# BLDC_DRIVER.net
KiCad netlist of a schematic drawn in EasyEDA Pro
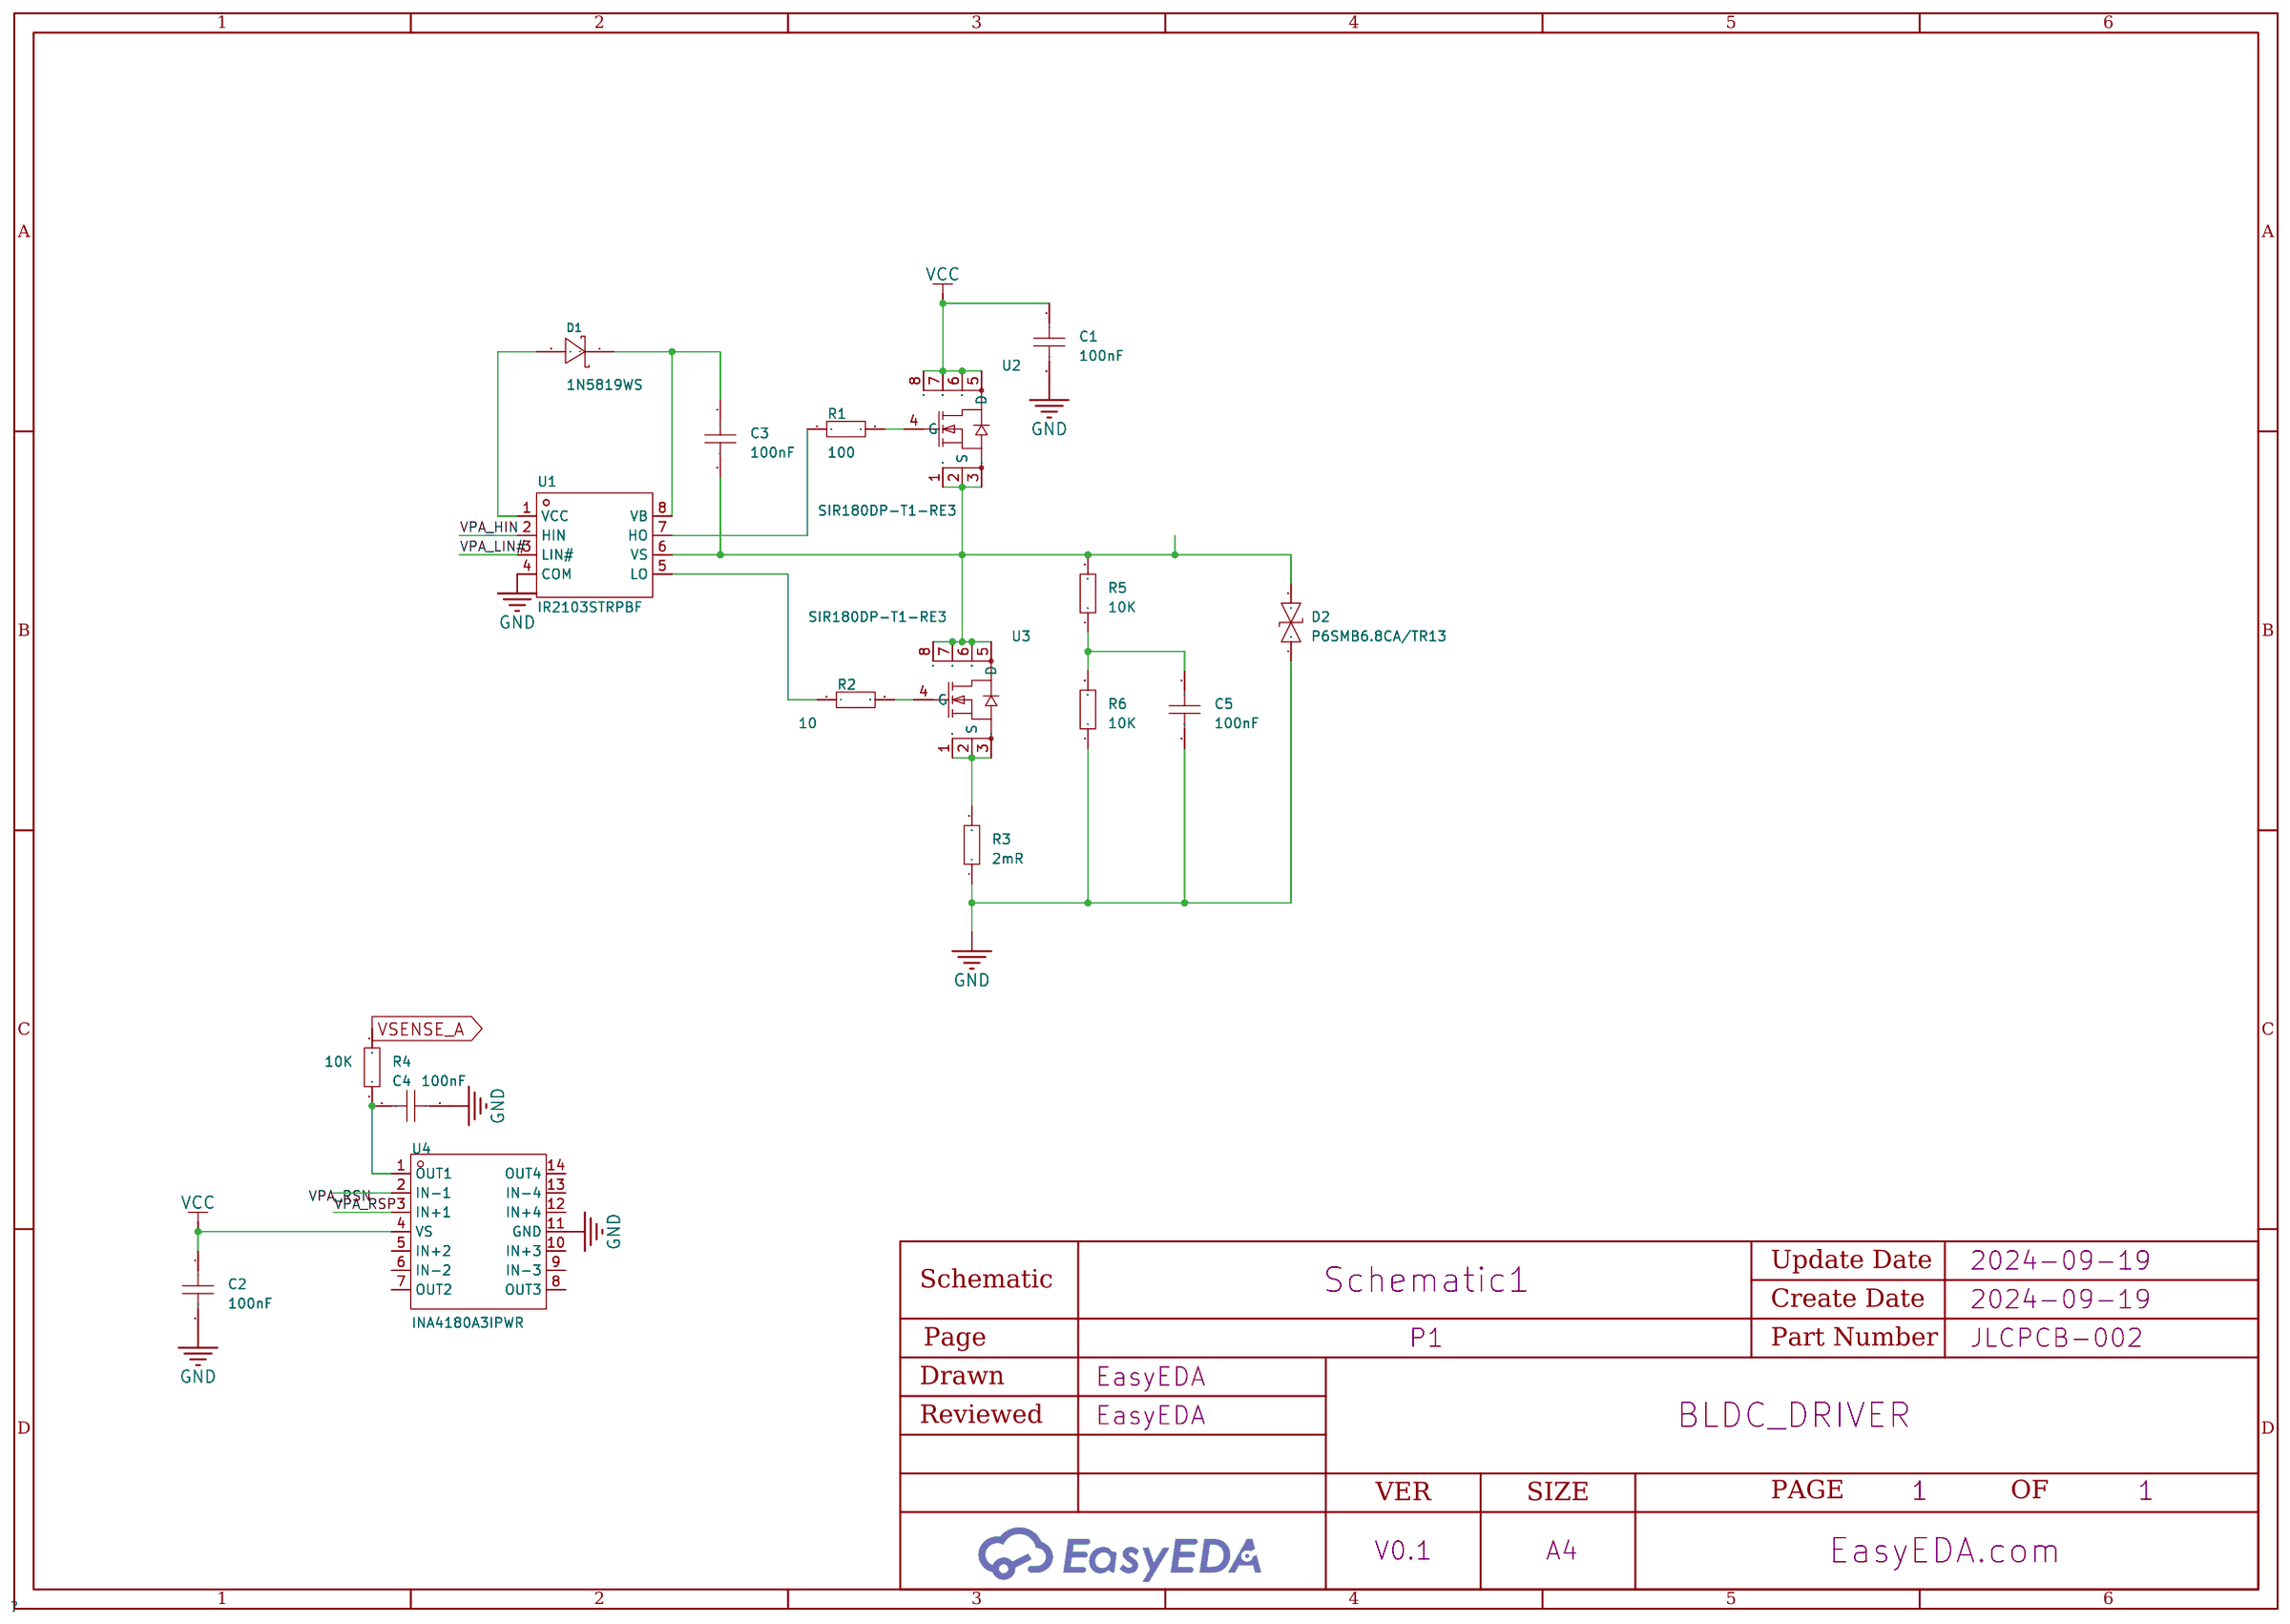
[diagram p0: schematic sheet]

(export (version "E")
  (design (tool "Eeschema 10.0.6"))
  (components
    (comp (ref "C1")
      (value "100nF")
      (footprint "easyedapro:C0603")
      (libsource (lib "easyedapro") (part "CAP"))
    )
    (comp (ref "C2")
      (value "100nF")
      (footprint "easyedapro:C0603")
      (libsource (lib "easyedapro") (part "CAP"))
    )
    (comp (ref "C3")
      (value "100nF")
      (footprint "easyedapro:C0603")
      (libsource (lib "easyedapro") (part "CAP"))
    )
    (comp (ref "C4")
      (value "100nF")
      (footprint "easyedapro:C0603")
      (libsource (lib "easyedapro") (part "CAP"))
    )
    (comp (ref "C5")
      (value "100nF")
      (footprint "easyedapro:C0603")
      (libsource (lib "easyedapro") (part "CAP"))
    )
    (comp (ref "D1")
      (value "1N5819WS")
      (footprint "easyedapro:SOD-323_L1.8-W1.3-LS2.5-RD")
      (description "Forward Voltage (Vf@If):600mV@1A Reverse Voltage (Vr):40V Average Rectified Current (Io):1A")
      (fields (field (name "Manufacturer") "Hottech(合科泰)"))
      (libsource (lib "easyedapro") (part "1N5819WS"))
    )
    (comp (ref "D2")
      (value "P6SMB6.8CA/TR13")
      (footprint "easyedapro:SMB_L4.6-W3.6-LS5.3-BI")
      (fields (field (name "Manufacturer") "Brightking(君耀电子)"))
      (libsource (lib "easyedapro") (part "P6SMB6.8CA-C78395"))
    )
    (comp (ref "R1") (value "100") (footprint "easyedapro:R0603") (libsource (lib "easyedapro") (part "Res")))
    (comp (ref "R2") (value "10") (footprint "easyedapro:R0603") (libsource (lib "easyedapro") (part "Res")))
    (comp (ref "R3") (value "2mR") (footprint "easyedapro:R0603") (libsource (lib "easyedapro") (part "Res")))
    (comp (ref "R4") (value "10K") (footprint "easyedapro:R0603") (libsource (lib "easyedapro") (part "Res")))
    (comp (ref "R5") (value "10K") (footprint "easyedapro:R0603") (libsource (lib "easyedapro") (part "Res")))
    (comp (ref "R6") (value "10K") (footprint "easyedapro:R0603") (libsource (lib "easyedapro") (part "Res")))
    (comp (ref "U1")
      (value "IR2103STRPBF")
      (footprint "easyedapro:SOIC-8_L4.9-W3.9-P1.27-LS6.0-BL")
      (fields (field (name "Manufacturer") "Infineon(英飞凌)"))
      (libsource (lib "easyedapro") (part "IR2103STRPBF"))
    )
    (comp (ref "U2")
      (value "SIR180DP-T1-RE3")
      (footprint "easyedapro:POWERPAK-SO-8_L5.9-W4.9-P1.27-LS6.2-BL")
      (fields (field (name "Manufacturer") "VISHAY(威世)"))
      (libsource (lib "easyedapro") (part "SIR180DP-T1-RE3"))
    )
    (comp (ref "U3")
      (value "SIR180DP-T1-RE3")
      (footprint "easyedapro:POWERPAK-SO-8_L5.9-W4.9-P1.27-LS6.2-BL")
      (fields (field (name "Manufacturer") "VISHAY(威世)"))
      (libsource (lib "easyedapro") (part "SIR180DP-T1-RE3"))
    )
    (comp (ref "U4")
      (value "INA4180A3IPWR")
      (footprint "easyedapro:TSSOP-14_L5.0-W4.4-P0.65-LS6.4-BL")
      (fields (field (name "Manufacturer") "TI(德州仪器)"))
      (libsource (lib "easyedapro") (part "INA4180A3IPWR"))
    )
  )
  (nets
    (net (code "1") (name "/VPA_HIN") (class "Default")
      (node (ref "U1") (pin "2") (pinfunction "HIN_2") (pintype "unspecified"))
    )
    (net (code "2") (name "/VPA_LIN#") (class "Default")
      (node (ref "U1") (pin "3") (pinfunction "LIN#_3") (pintype "unspecified"))
    )
    (net (code "3") (name "/VPA_RSN") (class "Default")
      (node (ref "U4") (pin "2") (pinfunction "IN-1_2") (pintype "unspecified"))
    )
    (net (code "4") (name "/VPA_RSP") (class "Default")
      (node (ref "U4") (pin "3") (pinfunction "IN+1_3") (pintype "unspecified"))
    )
    (net (code "5") (name "GND") (class "Default")
      (node (ref "C1") (pin "2") (pinfunction "2_2") (pintype "input"))
      (node (ref "C2") (pin "2") (pinfunction "2_2") (pintype "input"))
      (node (ref "C4") (pin "2") (pinfunction "2_2") (pintype "input"))
      (node (ref "C5") (pin "2") (pinfunction "2_2") (pintype "input"))
      (node (ref "D2") (pin "1") (pinfunction "1_1") (pintype "unspecified"))
      (node (ref "R3") (pin "1") (pinfunction "1_1") (pintype "input"))
      (node (ref "R6") (pin "1") (pinfunction "1_1") (pintype "input"))
      (node (ref "U1") (pin "4") (pinfunction "COM_4") (pintype "unspecified"))
      (node (ref "U4") (pin "11") (pinfunction "GND_11") (pintype "unspecified"))
    )
    (net (code "6") (name "Net-(C5-Pad1)") (class "Default")
      (node (ref "C5") (pin "1") (pinfunction "1_1") (pintype "input"))
      (node (ref "R5") (pin "1") (pinfunction "1_1") (pintype "input"))
      (node (ref "R6") (pin "2") (pinfunction "2_2") (pintype "input"))
    )
    (net (code "7") (name "Net-(D1-A)") (class "Default")
      (node (ref "D1") (pin "2") (pinfunction "A_2") (pintype "input"))
      (node (ref "U1") (pin "1") (pinfunction "VCC_1") (pintype "unspecified"))
    )
    (net (code "8") (name "Net-(D1-K)") (class "Default")
      (node (ref "C3") (pin "1") (pinfunction "1_1") (pintype "input"))
      (node (ref "D1") (pin "1") (pinfunction "K_1") (pintype "input"))
      (node (ref "U1") (pin "8") (pinfunction "VB_8") (pintype "unspecified"))
    )
    (net (code "9") (name "Net-(R3-Pad2)") (class "Default")
      (node (ref "R3") (pin "2") (pinfunction "2_2") (pintype "input"))
      (node (ref "U3") (pin "1") (pinfunction "S_1") (pintype "unspecified"))
      (node (ref "U3") (pin "2") (pinfunction "S_2") (pintype "unspecified"))
      (node (ref "U3") (pin "3") (pinfunction "S_3") (pintype "unspecified"))
    )
    (net (code "10") (name "Net-(U1-HO)") (class "Default")
      (node (ref "R1") (pin "1") (pinfunction "1_1") (pintype "input"))
      (node (ref "U1") (pin "7") (pinfunction "HO_7") (pintype "unspecified"))
    )
    (net (code "11") (name "Net-(U1-LO)") (class "Default")
      (node (ref "R2") (pin "1") (pinfunction "1_1") (pintype "input"))
      (node (ref "U1") (pin "5") (pinfunction "LO_5") (pintype "unspecified"))
    )
    (net (code "12") (name "Net-(U1-VS)") (class "Default")
      (node (ref "C3") (pin "2") (pinfunction "2_2") (pintype "input"))
      (node (ref "D2") (pin "2") (pinfunction "2_2") (pintype "unspecified"))
      (node (ref "R5") (pin "2") (pinfunction "2_2") (pintype "input"))
      (node (ref "U1") (pin "6") (pinfunction "VS_6") (pintype "unspecified"))
      (node (ref "U2") (pin "1") (pinfunction "S_1") (pintype "unspecified"))
      (node (ref "U2") (pin "2") (pinfunction "S_2") (pintype "unspecified"))
      (node (ref "U2") (pin "3") (pinfunction "S_3") (pintype "unspecified"))
      (node (ref "U3") (pin "5") (pinfunction "D_5") (pintype "unspecified"))
      (node (ref "U3") (pin "6") (pinfunction "D_6") (pintype "unspecified"))
      (node (ref "U3") (pin "7") (pinfunction "D_7") (pintype "unspecified"))
      (node (ref "U3") (pin "8") (pinfunction "D_8") (pintype "unspecified"))
    )
    (net (code "13") (name "Net-(U2-G)") (class "Default")
      (node (ref "R1") (pin "2") (pinfunction "2_2") (pintype "input"))
      (node (ref "U2") (pin "4") (pinfunction "G_4") (pintype "unspecified"))
    )
    (net (code "14") (name "Net-(U3-G)") (class "Default")
      (node (ref "R2") (pin "2") (pinfunction "2_2") (pintype "input"))
      (node (ref "U3") (pin "4") (pinfunction "G_4") (pintype "unspecified"))
    )
    (net (code "15") (name "Net-(U4-OUT1)") (class "Default")
      (node (ref "C4") (pin "1") (pinfunction "1_1") (pintype "input"))
      (node (ref "R4") (pin "2") (pinfunction "2_2") (pintype "input"))
      (node (ref "U4") (pin "1") (pinfunction "OUT1_1") (pintype "unspecified"))
    )
    (net (code "16") (name "VCC") (class "Default")
      (node (ref "C1") (pin "1") (pinfunction "1_1") (pintype "input"))
      (node (ref "C2") (pin "1") (pinfunction "1_1") (pintype "input"))
      (node (ref "U2") (pin "5") (pinfunction "D_5") (pintype "unspecified"))
      (node (ref "U2") (pin "6") (pinfunction "D_6") (pintype "unspecified"))
      (node (ref "U2") (pin "7") (pinfunction "D_7") (pintype "unspecified"))
      (node (ref "U2") (pin "8") (pinfunction "D_8") (pintype "unspecified"))
      (node (ref "U4") (pin "4") (pinfunction "VS_4") (pintype "unspecified"))
    )
    (net (code "17") (name "VSENSE_A") (class "Default")
      (node (ref "R4") (pin "1") (pinfunction "1_1") (pintype "input"))
    )
    (net (code "18") (name "unconnected-(U4-IN+2-Pad5)") (class "Default")
      (node (ref "U4") (pin "5") (pinfunction "IN+2_5") (pintype "unspecified"))
    )
    (net (code "19") (name "unconnected-(U4-IN+3-Pad10)") (class "Default")
      (node (ref "U4") (pin "10") (pinfunction "IN+3_10") (pintype "unspecified"))
    )
    (net (code "20") (name "unconnected-(U4-IN+4-Pad12)") (class "Default")
      (node (ref "U4") (pin "12") (pinfunction "IN+4_12") (pintype "unspecified"))
    )
    (net (code "21") (name "unconnected-(U4-IN-2-Pad6)") (class "Default")
      (node (ref "U4") (pin "6") (pinfunction "IN-2_6") (pintype "unspecified"))
    )
    (net (code "22") (name "unconnected-(U4-IN-3-Pad9)") (class "Default")
      (node (ref "U4") (pin "9") (pinfunction "IN-3_9") (pintype "unspecified"))
    )
    (net (code "23") (name "unconnected-(U4-IN-4-Pad13)") (class "Default")
      (node (ref "U4") (pin "13") (pinfunction "IN-4_13") (pintype "unspecified"))
    )
    (net (code "24") (name "unconnected-(U4-OUT2-Pad7)") (class "Default")
      (node (ref "U4") (pin "7") (pinfunction "OUT2_7") (pintype "unspecified"))
    )
    (net (code "25") (name "unconnected-(U4-OUT3-Pad8)") (class "Default")
      (node (ref "U4") (pin "8") (pinfunction "OUT3_8") (pintype "unspecified"))
    )
    (net (code "26") (name "unconnected-(U4-OUT4-Pad14)") (class "Default")
      (node (ref "U4") (pin "14") (pinfunction "OUT4_14") (pintype "unspecified"))
    )
  )
)
